# roma_rev_c.net
KiCad netlist of a schematic drawn in EAGLE
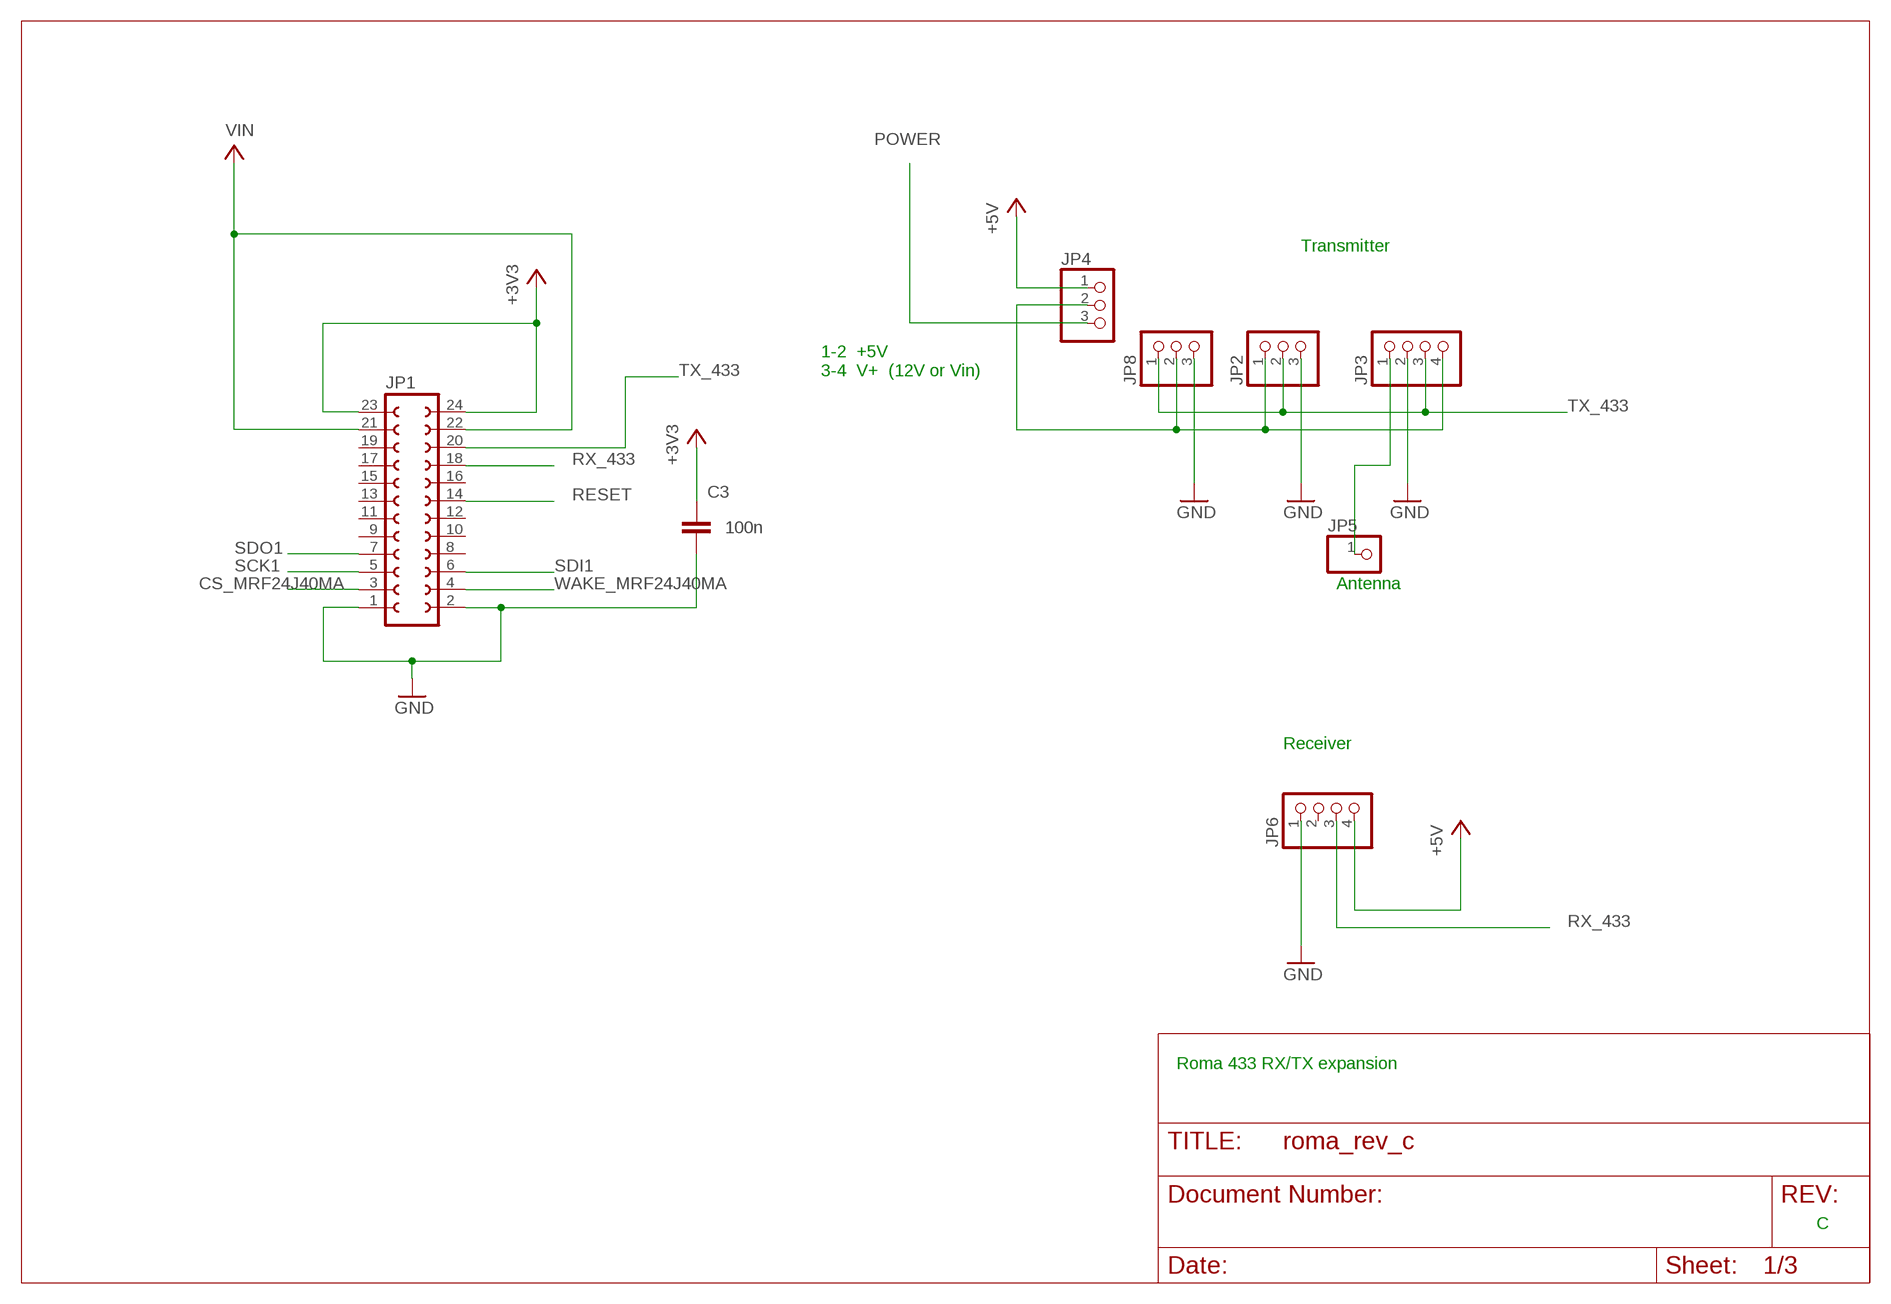
[diagram p0: schematic, sheet 1]
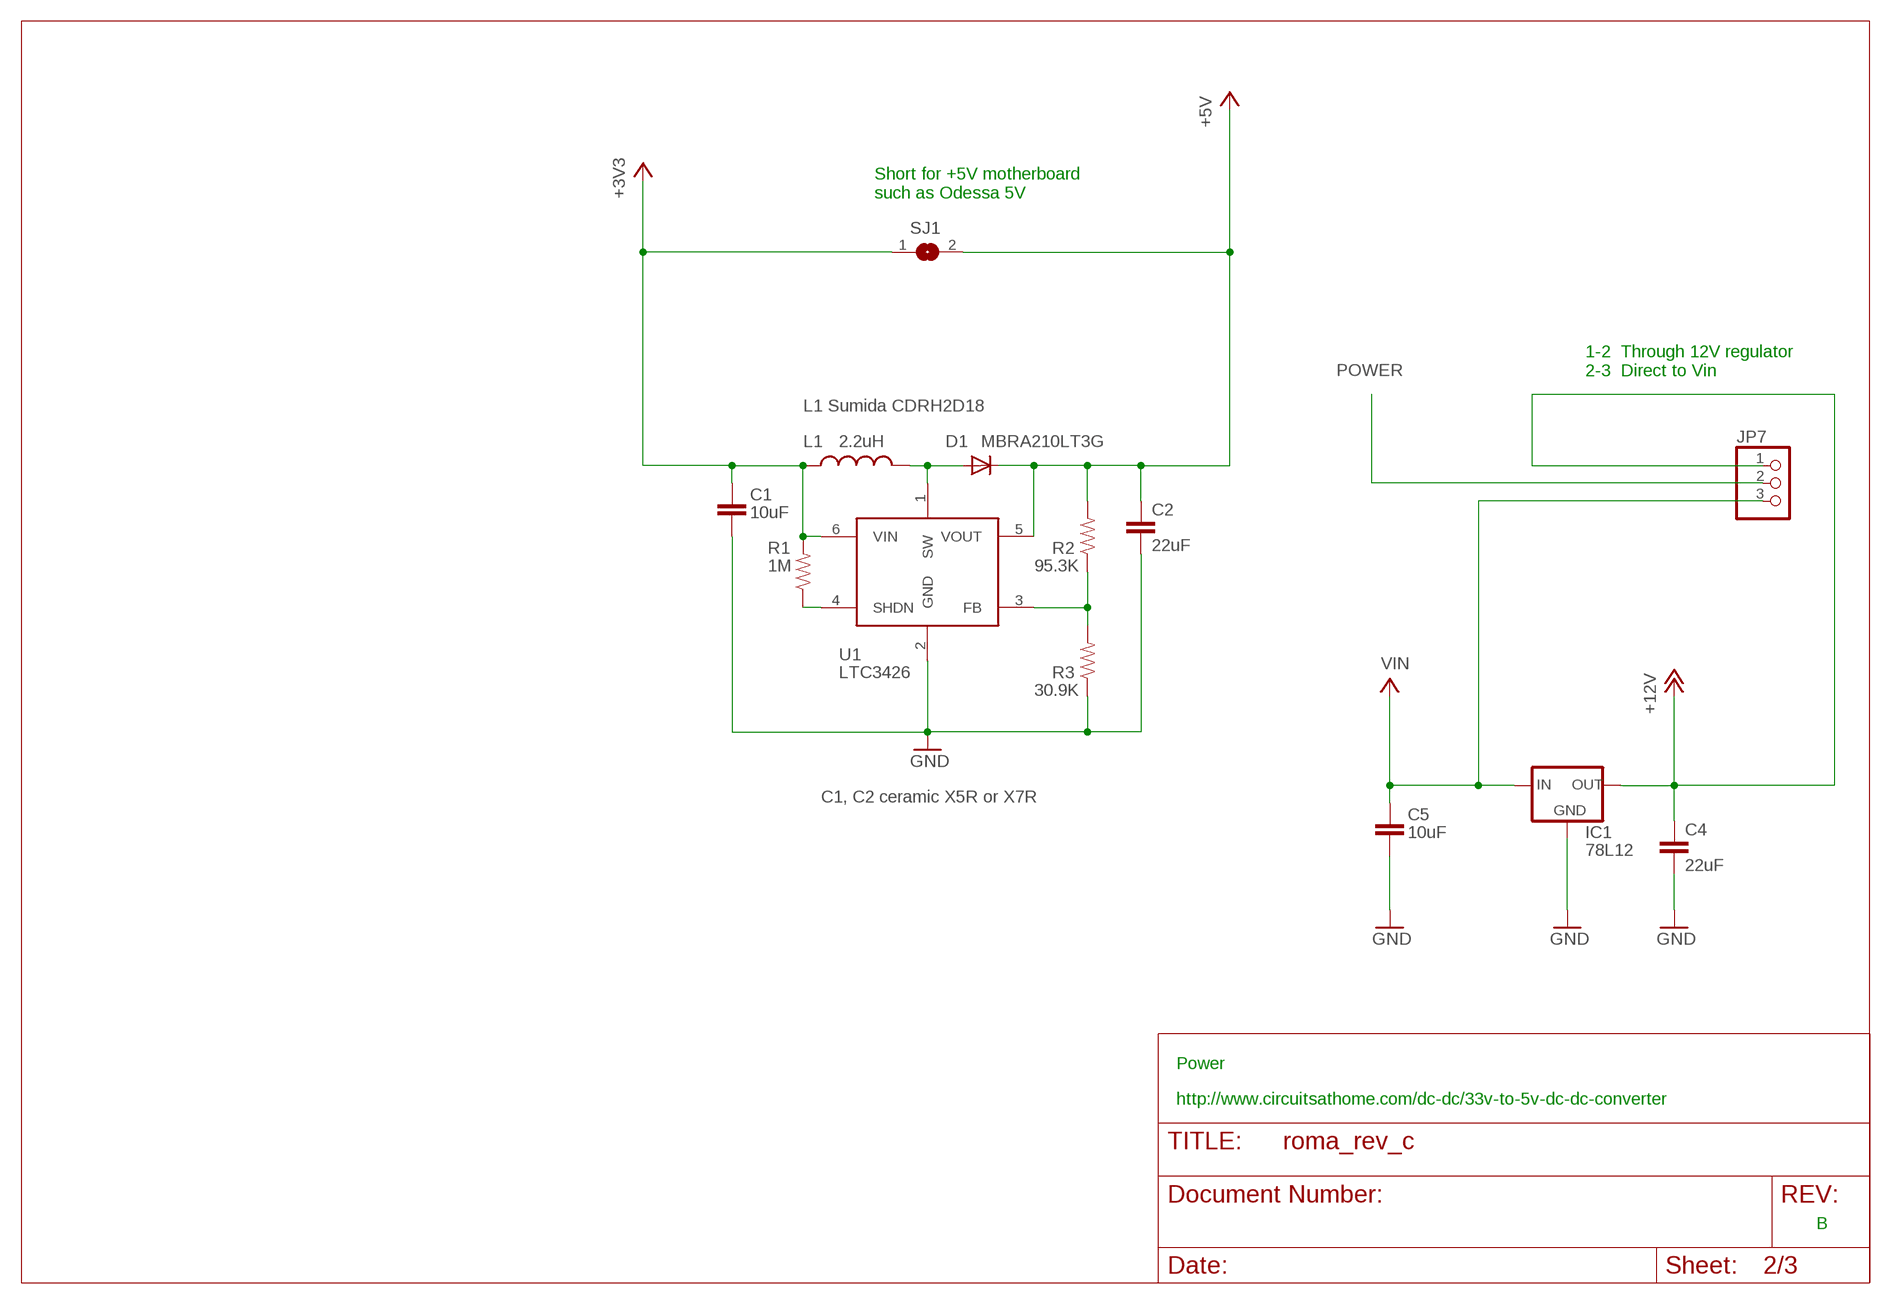
[diagram p1: schematic, sheet 2]
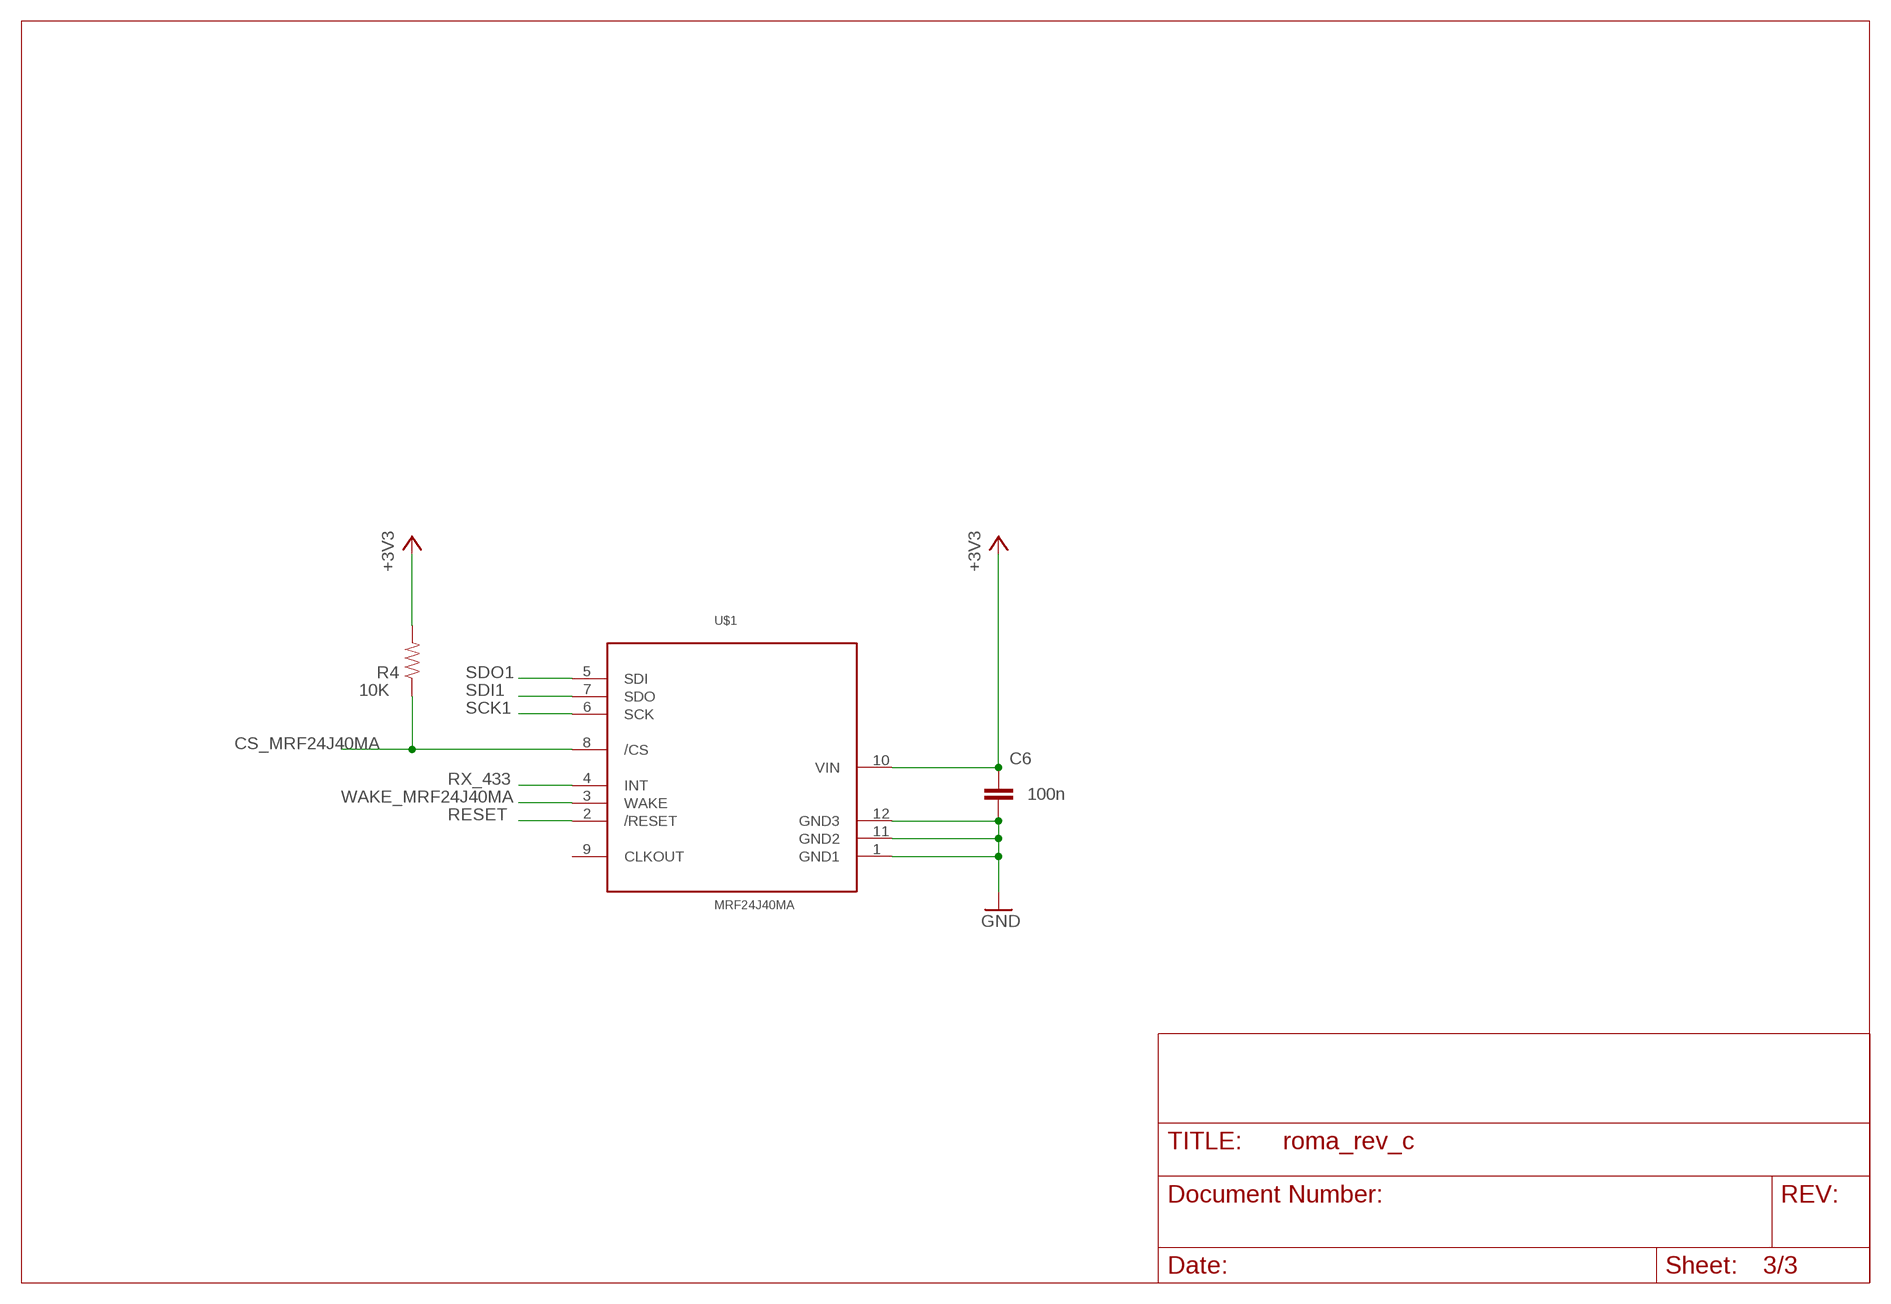
[diagram p2: schematic, sheet 3]

(export (version "E")
  (design (tool "Eeschema 10.0.6"))
  (components
    (comp (ref "C6")
      (value "100n")
      (footprint "eagle-import:C0805")
      (libsource (lib "eagle-import") (part "C-EUC0805"))
    )
    (comp (ref "R4")
      (value "10K")
      (footprint "eagle-import:0805")
      (libsource (lib "eagle-import") (part "RESISTOR0805"))
    )
    (comp (ref "U$1")
      (value "MRF24J40MA")
      (footprint "eagle-import:MRF24J40MA")
      (libsource (lib "eagle-import") (part "MRF24J40MA"))
    )
    (comp (ref "C1")
      (value "10uF")
      (footprint "eagle-import:1210")
      (libsource (lib "eagle-import") (part "CAP1210"))
    )
    (comp (ref "C2")
      (value "22uF")
      (footprint "eagle-import:1210")
      (libsource (lib "eagle-import") (part "CAP1210"))
    )
    (comp (ref "C4")
      (value "22uF")
      (footprint "eagle-import:1210")
      (libsource (lib "eagle-import") (part "CAP1210"))
    )
    (comp (ref "C5")
      (value "10uF")
      (footprint "eagle-import:1210")
      (libsource (lib "eagle-import") (part "CAP1210"))
    )
    (comp (ref "D1")
      (value "MBRA210LT3G")
      (footprint "eagle-import:SMA-DIODE")
      (libsource (lib "eagle-import") (part "DIODESMA"))
    )
    (comp (ref "IC1")
      (value "78L12")
      (footprint "eagle-import:78LXX")
      (libsource (lib "eagle-import") (part "78LXX"))
    )
    (comp (ref "JP7")
      (value "PINHD-1X3")
      (footprint "eagle-import:1X03")
      (libsource (lib "eagle-import") (part "PINHD-1X3"))
    )
    (comp (ref "L1")
      (value "2.2uH")
      (footprint "eagle-import:1_3X1_3")
      (libsource (lib "eagle-import") (part "INDUCTOR1313"))
    )
    (comp (ref "R1")
      (value "1M")
      (footprint "eagle-import:0805")
      (libsource (lib "eagle-import") (part "RESISTOR0805"))
    )
    (comp (ref "R2")
      (value "95.3K")
      (footprint "eagle-import:0805")
      (libsource (lib "eagle-import") (part "RESISTOR0805"))
    )
    (comp (ref "R3")
      (value "30.9K")
      (footprint "eagle-import:0805")
      (libsource (lib "eagle-import") (part "RESISTOR0805"))
    )
    (comp (ref "SJ1") (value "SJ") (footprint "eagle-import:SJ") (libsource (lib "eagle-import") (part "SJ")))
    (comp (ref "U1")
      (value "LTC3426")
      (footprint "eagle-import:SOT23-6")
      (libsource (lib "eagle-import") (part "LTC3426"))
    )
    (comp (ref "C3")
      (value "100n")
      (footprint "eagle-import:C0805")
      (libsource (lib "eagle-import") (part "C-EUC0805"))
    )
    (comp (ref "JP1")
      (value "FE12-2")
      (footprint "eagle-import:FE12-2")
      (libsource (lib "eagle-import") (part "FE12-2"))
    )
    (comp (ref "JP2")
      (value "PINHD-1X3")
      (footprint "eagle-import:1X03")
      (libsource (lib "eagle-import") (part "PINHD-1X3"))
    )
    (comp (ref "JP3")
      (value "PINHD-1X4")
      (footprint "eagle-import:1X04")
      (libsource (lib "eagle-import") (part "PINHD-1X4"))
    )
    (comp (ref "JP4")
      (value "PINHD-1X3")
      (footprint "eagle-import:1X03")
      (libsource (lib "eagle-import") (part "PINHD-1X3"))
    )
    (comp (ref "JP5")
      (value "PINHD-1X1")
      (footprint "eagle-import:1X01")
      (libsource (lib "eagle-import") (part "PINHD-1X1"))
    )
    (comp (ref "JP6")
      (value "PINHD-1X4")
      (footprint "eagle-import:1X04")
      (libsource (lib "eagle-import") (part "PINHD-1X4"))
    )
    (comp (ref "JP8")
      (value "PINHD-1X3")
      (footprint "eagle-import:1X03")
      (libsource (lib "eagle-import") (part "PINHD-1X3"))
    )
  )
  (nets
    (net (code "1") (name "+3V3") (class "Default")
      (node (ref "C1") (pin "1") (pinfunction "1_1") (pintype "passive"))
      (node (ref "C3") (pin "1") (pinfunction "1_1") (pintype "passive"))
      (node (ref "C6") (pin "1") (pinfunction "1_1") (pintype "passive"))
      (node (ref "JP1") (pin "23") (pinfunction "23_23") (pintype "passive"))
      (node (ref "JP1") (pin "24") (pinfunction "24_24") (pintype "passive"))
      (node (ref "L1") (pin "P$1") (pinfunction "1_P$1") (pintype "passive"))
      (node (ref "R1") (pin "2") (pinfunction "2_2") (pintype "passive"))
      (node (ref "R4") (pin "2") (pinfunction "2_2") (pintype "passive"))
      (node (ref "SJ1") (pin "1") (pinfunction "1_1") (pintype "passive"))
      (node (ref "U$1") (pin "10") (pinfunction "VIN_10") (pintype "power_in"))
      (node (ref "U1") (pin "6") (pinfunction "VIN_6") (pintype "power_in"))
    )
    (net (code "2") (name "+5V") (class "Default")
      (node (ref "C2") (pin "1") (pinfunction "1_1") (pintype "passive"))
      (node (ref "D1") (pin "C") (pinfunction "C_C") (pintype "passive"))
      (node (ref "JP4") (pin "1") (pinfunction "1_1") (pintype "passive"))
      (node (ref "JP6") (pin "4") (pinfunction "4_4") (pintype "passive"))
      (node (ref "R2") (pin "2") (pinfunction "2_2") (pintype "passive"))
      (node (ref "SJ1") (pin "2") (pinfunction "2_2") (pintype "passive"))
      (node (ref "U1") (pin "5") (pinfunction "VOUT_5") (pintype "passive"))
    )
    (net (code "3") (name "+12V") (class "Default")
      (node (ref "C4") (pin "1") (pinfunction "1_1") (pintype "passive"))
      (node (ref "IC1") (pin "OUT") (pinfunction "OUT_OUT") (pintype "passive"))
      (node (ref "JP7") (pin "1") (pinfunction "1_1") (pintype "passive"))
    )
    (net (code "4") (name "CS_MRF24J40MA") (class "Default")
      (node (ref "JP1") (pin "3") (pinfunction "3_3") (pintype "passive"))
      (node (ref "R4") (pin "1") (pinfunction "1_1") (pintype "passive"))
      (node (ref "U$1") (pin "8") (pinfunction "/CS_8") (pintype "bidirectional"))
    )
    (net (code "5") (name "GND") (class "Default")
      (node (ref "C1") (pin "2") (pinfunction "2_2") (pintype "passive"))
      (node (ref "C2") (pin "2") (pinfunction "2_2") (pintype "passive"))
      (node (ref "C3") (pin "2") (pinfunction "2_2") (pintype "passive"))
      (node (ref "C4") (pin "2") (pinfunction "2_2") (pintype "passive"))
      (node (ref "C5") (pin "2") (pinfunction "2_2") (pintype "passive"))
      (node (ref "C6") (pin "2") (pinfunction "2_2") (pintype "passive"))
      (node (ref "IC1") (pin "GND") (pinfunction "GND_GND") (pintype "input"))
      (node (ref "JP1") (pin "1") (pinfunction "1_1") (pintype "passive"))
      (node (ref "JP1") (pin "2") (pinfunction "2_2") (pintype "passive"))
      (node (ref "JP2") (pin "3") (pinfunction "3_3") (pintype "passive"))
      (node (ref "JP3") (pin "2") (pinfunction "2_2") (pintype "passive"))
      (node (ref "JP6") (pin "1") (pinfunction "1_1") (pintype "passive"))
      (node (ref "JP8") (pin "3") (pinfunction "3_3") (pintype "passive"))
      (node (ref "R3") (pin "1") (pinfunction "1_1") (pintype "passive"))
      (node (ref "U$1") (pin "1") (pinfunction "GND1_1") (pintype "power_in"))
      (node (ref "U$1") (pin "11") (pinfunction "GND2_11") (pintype "power_in"))
      (node (ref "U$1") (pin "12") (pinfunction "GND3_12") (pintype "power_in"))
      (node (ref "U1") (pin "2") (pinfunction "GND_2") (pintype "passive"))
    )
    (net (code "6") (name "Net-(JP2-Pad1)") (class "Default")
      (node (ref "JP2") (pin "1") (pinfunction "1_1") (pintype "passive"))
      (node (ref "JP3") (pin "4") (pinfunction "4_4") (pintype "passive"))
      (node (ref "JP4") (pin "2") (pinfunction "2_2") (pintype "passive"))
      (node (ref "JP8") (pin "2") (pinfunction "2_2") (pintype "passive"))
    )
    (net (code "7") (name "Net-(JP3-Pad1)") (class "Default")
      (node (ref "JP3") (pin "1") (pinfunction "1_1") (pintype "passive"))
      (node (ref "JP5") (pin "1") (pinfunction "1_1") (pintype "passive"))
    )
    (net (code "8") (name "Net-(L1-2)") (class "Default")
      (node (ref "D1") (pin "A") (pinfunction "A_A") (pintype "passive"))
      (node (ref "L1") (pin "P$2") (pinfunction "2_P$2") (pintype "passive"))
      (node (ref "U1") (pin "1") (pinfunction "SW_1") (pintype "passive"))
    )
    (net (code "9") (name "Net-(U1-FB)") (class "Default")
      (node (ref "R2") (pin "1") (pinfunction "1_1") (pintype "passive"))
      (node (ref "R3") (pin "2") (pinfunction "2_2") (pintype "passive"))
      (node (ref "U1") (pin "3") (pinfunction "FB_3") (pintype "input"))
    )
    (net (code "10") (name "Net-(U1-SHDN)") (class "Default")
      (node (ref "R1") (pin "1") (pinfunction "1_1") (pintype "passive"))
      (node (ref "U1") (pin "4") (pinfunction "SHDN_4") (pintype "input"))
    )
    (net (code "11") (name "POWER") (class "Default")
      (node (ref "JP4") (pin "3") (pinfunction "3_3") (pintype "passive"))
      (node (ref "JP7") (pin "2") (pinfunction "2_2") (pintype "passive"))
    )
    (net (code "12") (name "RESET") (class "Default")
      (node (ref "JP1") (pin "14") (pinfunction "14_14") (pintype "passive"))
      (node (ref "U$1") (pin "2") (pinfunction "/RESET_2") (pintype "bidirectional"))
    )
    (net (code "13") (name "RX_433") (class "Default")
      (node (ref "JP1") (pin "18") (pinfunction "18_18") (pintype "passive"))
      (node (ref "JP6") (pin "3") (pinfunction "3_3") (pintype "passive"))
      (node (ref "U$1") (pin "4") (pinfunction "INT_4") (pintype "bidirectional"))
    )
    (net (code "14") (name "SCK1") (class "Default")
      (node (ref "JP1") (pin "5") (pinfunction "5_5") (pintype "passive"))
      (node (ref "U$1") (pin "6") (pinfunction "SCK_6") (pintype "bidirectional"))
    )
    (net (code "15") (name "SDI1") (class "Default")
      (node (ref "JP1") (pin "6") (pinfunction "6_6") (pintype "passive"))
      (node (ref "U$1") (pin "7") (pinfunction "SDO_7") (pintype "bidirectional"))
    )
    (net (code "16") (name "SDO1") (class "Default")
      (node (ref "JP1") (pin "7") (pinfunction "7_7") (pintype "passive"))
      (node (ref "U$1") (pin "5") (pinfunction "SDI_5") (pintype "bidirectional"))
    )
    (net (code "17") (name "TX_433") (class "Default")
      (node (ref "JP1") (pin "20") (pinfunction "20_20") (pintype "passive"))
      (node (ref "JP2") (pin "2") (pinfunction "2_2") (pintype "passive"))
      (node (ref "JP3") (pin "3") (pinfunction "3_3") (pintype "passive"))
      (node (ref "JP8") (pin "1") (pinfunction "1_1") (pintype "passive"))
    )
    (net (code "18") (name "VIN") (class "Default")
      (node (ref "C5") (pin "1") (pinfunction "1_1") (pintype "passive"))
      (node (ref "IC1") (pin "IN") (pinfunction "IN_IN") (pintype "input"))
      (node (ref "JP1") (pin "21") (pinfunction "21_21") (pintype "passive"))
      (node (ref "JP1") (pin "22") (pinfunction "22_22") (pintype "passive"))
      (node (ref "JP7") (pin "3") (pinfunction "3_3") (pintype "passive"))
    )
    (net (code "19") (name "WAKE_MRF24J40MA") (class "Default")
      (node (ref "JP1") (pin "4") (pinfunction "4_4") (pintype "passive"))
      (node (ref "U$1") (pin "3") (pinfunction "WAKE_3") (pintype "bidirectional"))
    )
    (net (code "20") (name "unconnected-(JP1-Pad8)") (class "Default")
      (node (ref "JP1") (pin "8") (pinfunction "8_8") (pintype "passive"))
    )
    (net (code "21") (name "unconnected-(JP1-Pad9)") (class "Default")
      (node (ref "JP1") (pin "9") (pinfunction "9_9") (pintype "passive"))
    )
    (net (code "22") (name "unconnected-(JP1-Pad10)") (class "Default")
      (node (ref "JP1") (pin "10") (pinfunction "10_10") (pintype "passive"))
    )
    (net (code "23") (name "unconnected-(JP1-Pad11)") (class "Default")
      (node (ref "JP1") (pin "11") (pinfunction "11_11") (pintype "passive"))
    )
    (net (code "24") (name "unconnected-(JP1-Pad12)") (class "Default")
      (node (ref "JP1") (pin "12") (pinfunction "12_12") (pintype "passive"))
    )
    (net (code "25") (name "unconnected-(JP1-Pad13)") (class "Default")
      (node (ref "JP1") (pin "13") (pinfunction "13_13") (pintype "passive"))
    )
    (net (code "26") (name "unconnected-(JP1-Pad15)") (class "Default")
      (node (ref "JP1") (pin "15") (pinfunction "15_15") (pintype "passive"))
    )
    (net (code "27") (name "unconnected-(JP1-Pad16)") (class "Default")
      (node (ref "JP1") (pin "16") (pinfunction "16_16") (pintype "passive"))
    )
    (net (code "28") (name "unconnected-(JP1-Pad17)") (class "Default")
      (node (ref "JP1") (pin "17") (pinfunction "17_17") (pintype "passive"))
    )
    (net (code "29") (name "unconnected-(JP1-Pad19)") (class "Default")
      (node (ref "JP1") (pin "19") (pinfunction "19_19") (pintype "passive"))
    )
    (net (code "30") (name "unconnected-(JP6-Pad2)") (class "Default")
      (node (ref "JP6") (pin "2") (pinfunction "2_2") (pintype "passive"))
    )
    (net (code "31") (name "unconnected-(U$1-CLKOUT-Pad9)") (class "Default")
      (node (ref "U$1") (pin "9") (pinfunction "CLKOUT_9") (pintype "output"))
    )
  )
)
